# Interface.net
KiCad netlist of a schematic drawn in Altium Designer
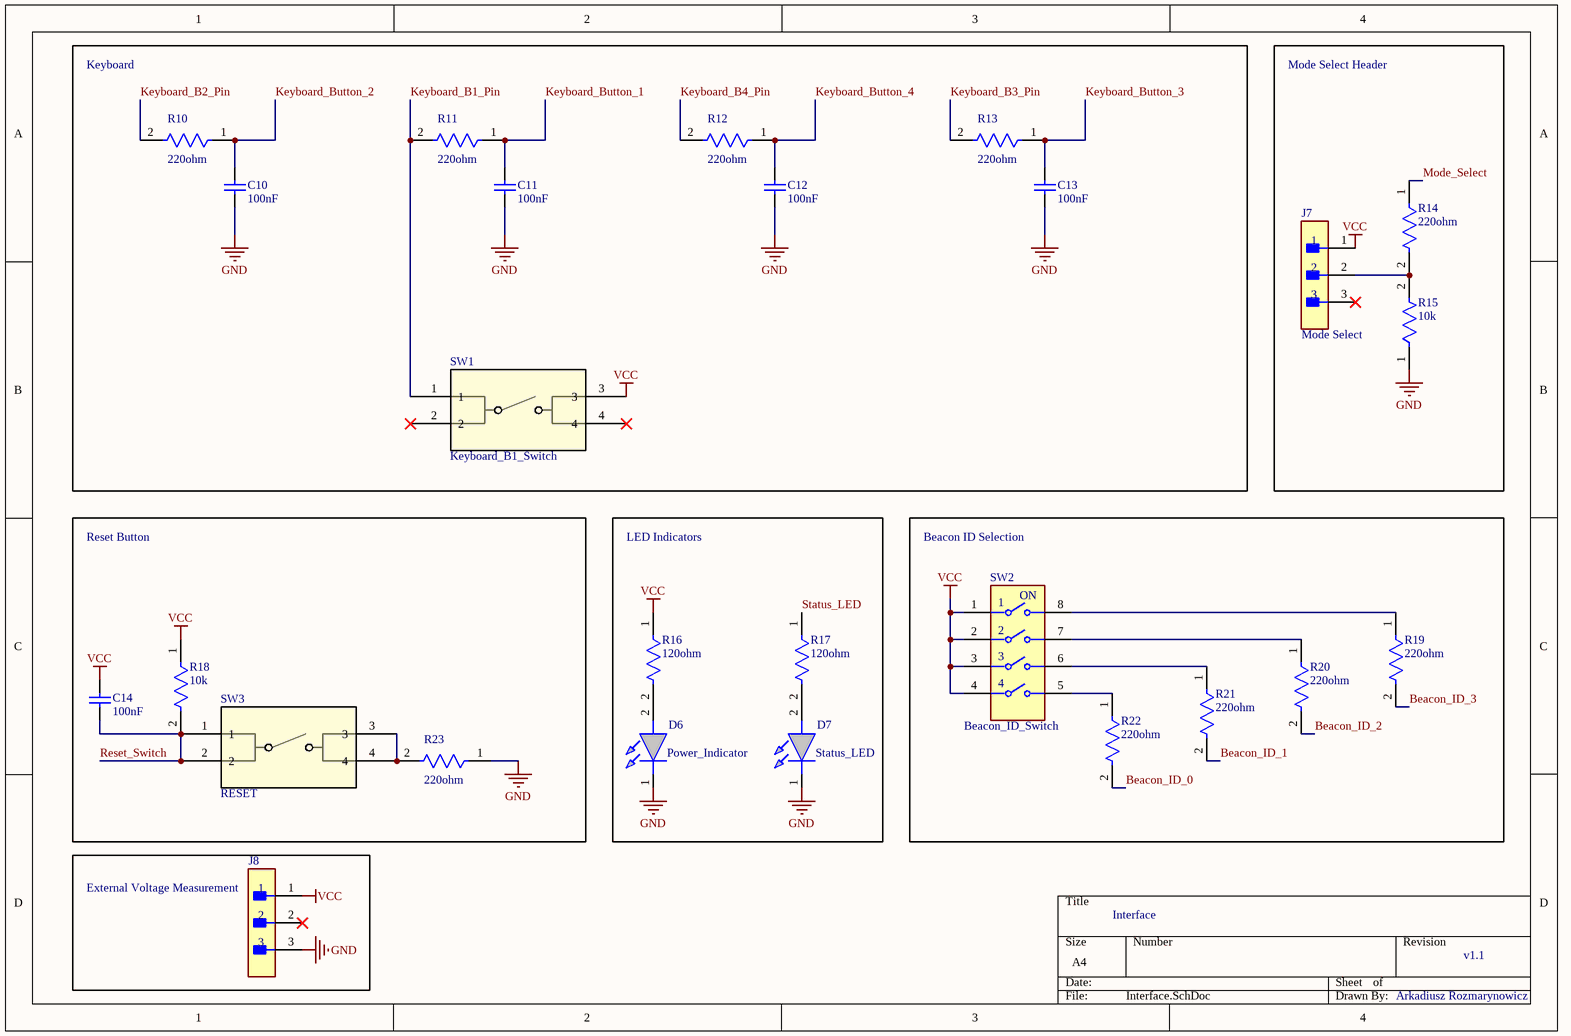
[diagram p0: Interface.SchDoc]

(export (version "E")
  (design (tool "Eeschema 10.0.6"))
  (components
    (comp (ref "C10")
      (value "100nF")
      (footprint "CAPC2013X145X48NL20T23")
      (fields (field (name "PART NUMBER") "VJ0805Y104KXAMR") (field (name "MANUFACTURER") "Vitramon"))
      (libsource (lib "Altium Content Vault") (part "CAP"))
    )
    (comp (ref "C11")
      (value "100nF")
      (footprint "CAPC2013X145X48NL20T23")
      (fields (field (name "PART NUMBER") "VJ0805Y104KXAMR") (field (name "MANUFACTURER") "Vitramon"))
      (libsource (lib "Altium Content Vault") (part "CAP"))
    )
    (comp (ref "C12")
      (value "100nF")
      (footprint "CAPC2013X145X48NL20T23")
      (fields (field (name "PART NUMBER") "VJ0805Y104KXAMR") (field (name "MANUFACTURER") "Vitramon"))
      (libsource (lib "Altium Content Vault") (part "CAP"))
    )
    (comp (ref "C13")
      (value "100nF")
      (footprint "CAPC2013X145X48NL20T23")
      (fields (field (name "PART NUMBER") "VJ0805Y104KXAMR") (field (name "MANUFACTURER") "Vitramon"))
      (libsource (lib "Altium Content Vault") (part "CAP"))
    )
    (comp (ref "C14")
      (value "100nF")
      (footprint "CAPC2013X145X48NL20T23")
      (fields (field (name "PART NUMBER") "VJ0805Y104KXAMR") (field (name "MANUFACTURER") "Vitramon"))
      (libsource (lib "Altium Content Vault") (part "CAP"))
    )
    (comp (ref "D6")
      (value "Power_Indicator")
      (footprint "LEDC2012X40N")
      (fields
        (field (name "MANUFACTURER_PART_NUMBER") "LS R976")
        (field (name "MOUSER PART NUMBER") "720-LSR976D5178")
      )
      (libsource (lib "LS_R976") (part "LS_R976"))
    )
    (comp (ref "D7")
      (value "Status_LED")
      (footprint "LEDC2012X40N")
      (fields
        (field (name "MANUFACTURER_PART_NUMBER") "LS R976")
        (field (name "MOUSER PART NUMBER") "720-LSR976D5178")
      )
      (libsource (lib "LS_R976") (part "LS_R976"))
    )
    (comp (ref "J7")
      (value "Mode Select")
      (footprint "FP-TMM-103-03-T-S-MFG")
      (description "CONN HEADER VERT 3POS 2MM")
      (libsource (lib "Altium Content Vault") (part "0d3f023dd272f625e17a2be33dea85f"))
    )
    (comp (ref "J8")
      (value "External Voltage Measurement")
      (footprint "FP-TMM-103-03-T-S-MFG")
      (description "CONN HEADER VERT 3POS 2MM")
      (libsource (lib "Altium Content Vault") (part "0d3f023dd272f625e17a2be33dea85f"))
    )
    (comp (ref "R10")
      (value "220ohm")
      (footprint "FP-CRGCQ0805-IPC_C")
      (description "CRGCQ0805 100KΩ 0.125W ±100ppm/°C 5% 150V")
      (fields
        (field (name "TOLERANCE") "0.05")
        (field (name "OCTOPART") "https://octopart.com/crgcq0805j100k-te+connectivity-91018199")
      )
      (libsource (lib "Altium Content Vault") (part "1029c3af85768c4190bb7ad29bc67b5"))
    )
    (comp (ref "R11")
      (value "220ohm")
      (footprint "FP-CRGCQ0805-IPC_C")
      (description "CRGCQ0805 100KΩ 0.125W ±100ppm/°C 5% 150V")
      (fields
        (field (name "TOLERANCE") "0.05")
        (field (name "OCTOPART") "https://octopart.com/crgcq0805j100k-te+connectivity-91018199")
      )
      (libsource (lib "Altium Content Vault") (part "1029c3af85768c4190bb7ad29bc67b5"))
    )
    (comp (ref "R12")
      (value "220ohm")
      (footprint "FP-CRGCQ0805-IPC_C")
      (description "CRGCQ0805 100KΩ 0.125W ±100ppm/°C 5% 150V")
      (fields
        (field (name "TOLERANCE") "0.05")
        (field (name "OCTOPART") "https://octopart.com/crgcq0805j100k-te+connectivity-91018199")
      )
      (libsource (lib "Altium Content Vault") (part "1029c3af85768c4190bb7ad29bc67b5"))
    )
    (comp (ref "R13")
      (value "220ohm")
      (footprint "FP-CRGCQ0805-IPC_C")
      (description "CRGCQ0805 100KΩ 0.125W ±100ppm/°C 5% 150V")
      (fields
        (field (name "TOLERANCE") "0.05")
        (field (name "OCTOPART") "https://octopart.com/crgcq0805j100k-te+connectivity-91018199")
      )
      (libsource (lib "Altium Content Vault") (part "1029c3af85768c4190bb7ad29bc67b5"))
    )
    (comp (ref "R14")
      (value "220ohm")
      (footprint "FP-CRGCQ0805-IPC_C")
      (description "CRGCQ0805 10KΩ 0.125W ±100ppm/°C 5% 150V")
      (fields
        (field (name "TOLERANCE") "0.05")
        (field (name "OCTOPART") "https://octopart.com/crgcq0805j100k-te+connectivity-91018199")
      )
      (libsource (lib "Altium Content Vault") (part "1029c3af85768c4190bb7ad29bc67b5"))
    )
    (comp (ref "R15")
      (value "10k")
      (footprint "FP-CRGCQ0805-IPC_C")
      (description "CRGCQ0805 10KΩ 0.125W ±100ppm/°C 5% 150V")
      (fields
        (field (name "TOLERANCE") "0.05")
        (field (name "OCTOPART") "https://octopart.com/crgcq0805j100k-te+connectivity-91018199")
      )
      (libsource (lib "Altium Content Vault") (part "1029c3af85768c4190bb7ad29bc67b5"))
    )
    (comp (ref "R16")
      (value "120ohm")
      (footprint "FP-CRGCQ0805-IPC_C")
      (description "CRGCQ0805 100KΩ 0.125W ±100ppm/°C 5% 150V")
      (fields
        (field (name "TOLERANCE") "0.05")
        (field (name "OCTOPART") "https://octopart.com/crgcq0805j100k-te+connectivity-91018199")
      )
      (libsource (lib "Altium Content Vault") (part "1029c3af85768c4190bb7ad29bc67b5"))
    )
    (comp (ref "R17")
      (value "120ohm")
      (footprint "FP-CRGCQ0805-IPC_C")
      (description "CRGCQ0805 100KΩ 0.125W ±100ppm/°C 5% 150V")
      (fields
        (field (name "TOLERANCE") "0.05")
        (field (name "OCTOPART") "https://octopart.com/crgcq0805j100k-te+connectivity-91018199")
      )
      (libsource (lib "Altium Content Vault") (part "1029c3af85768c4190bb7ad29bc67b5"))
    )
    (comp (ref "R18")
      (value "10k")
      (footprint "FP-CRGCQ0805-IPC_C")
      (description "CRGCQ0805 10KΩ 0.125W ±100ppm/°C 5% 150V")
      (fields
        (field (name "TOLERANCE") "0.05")
        (field (name "OCTOPART") "https://octopart.com/crgcq0805j100k-te+connectivity-91018199")
      )
      (libsource (lib "Altium Content Vault") (part "1029c3af85768c4190bb7ad29bc67b5"))
    )
    (comp (ref "R19")
      (value "220ohm")
      (footprint "FP-CRGCQ0805-IPC_C")
      (description "CRGCQ0805 10KΩ 0.125W ±100ppm/°C 5% 150V")
      (fields
        (field (name "TOLERANCE") "0.05")
        (field (name "OCTOPART") "https://octopart.com/crgcq0805j100k-te+connectivity-91018199")
      )
      (libsource (lib "Altium Content Vault") (part "1029c3af85768c4190bb7ad29bc67b5"))
    )
    (comp (ref "R20")
      (value "220ohm")
      (footprint "FP-CRGCQ0805-IPC_C")
      (description "CRGCQ0805 10KΩ 0.125W ±100ppm/°C 5% 150V")
      (fields
        (field (name "TOLERANCE") "0.05")
        (field (name "OCTOPART") "https://octopart.com/crgcq0805j100k-te+connectivity-91018199")
      )
      (libsource (lib "Altium Content Vault") (part "1029c3af85768c4190bb7ad29bc67b5"))
    )
    (comp (ref "R21")
      (value "220ohm")
      (footprint "FP-CRGCQ0805-IPC_C")
      (description "CRGCQ0805 10KΩ 0.125W ±100ppm/°C 5% 150V")
      (fields
        (field (name "TOLERANCE") "0.05")
        (field (name "OCTOPART") "https://octopart.com/crgcq0805j100k-te+connectivity-91018199")
      )
      (libsource (lib "Altium Content Vault") (part "1029c3af85768c4190bb7ad29bc67b5"))
    )
    (comp (ref "R22")
      (value "220ohm")
      (footprint "FP-CRGCQ0805-IPC_C")
      (description "CRGCQ0805 10KΩ 0.125W ±100ppm/°C 5% 150V")
      (fields
        (field (name "TOLERANCE") "0.05")
        (field (name "OCTOPART") "https://octopart.com/crgcq0805j100k-te+connectivity-91018199")
      )
      (libsource (lib "Altium Content Vault") (part "1029c3af85768c4190bb7ad29bc67b5"))
    )
    (comp (ref "R23")
      (value "220ohm")
      (footprint "FP-CRGCQ0805-IPC_C")
      (description "CRGCQ0805 100KΩ 0.125W ±100ppm/°C 5% 150V")
      (fields
        (field (name "TOLERANCE") "0.05")
        (field (name "OCTOPART") "https://octopart.com/crgcq0805j100k-te+connectivity-91018199")
      )
      (libsource (lib "Altium Content Vault") (part "1029c3af85768c4190bb7ad29bc67b5"))
    )
    (comp (ref "SW1")
      (value "Keyboard_B1_Switch")
      (footprint "SW4_FSM-5P23_TEC")
      (description "FSM4JSMAATR=TACTSWITCH,SMT,T&R")
      (fields
        (field (name "MANUFACTURER_PART_NUMBER") "1571563-4")
        (field (name "COPYRIGHT") "Copyright (C) 2025 Ultra Librarian. All rights reserved.")
      )
      (libsource (lib "FSM4JSMAATR") (part "1571563-4"))
    )
    (comp (ref "SW2")
      (value "Beacon_ID_Switch")
      (footprint "FP-A6S-4104-H-MFG")
      (description "SWITCH SLIDE DIP SPST 25MA 24V")
      (fields
        (field (name "OCTOPART") "https://octopart.com/a6s-4104-h-omron-1480027")
        (field (name "MANUFACTURER PART NUMBER") "A6S-4104-H")
      )
      (libsource (lib "Altium Content Vault") (part "113dad22f56f77360964ee595240726"))
    )
    (comp (ref "SW3")
      (value "RESET")
      (footprint "SW4_FSM-5P23_TEC")
      (description "FSM4JSMAATR=TACTSWITCH,SMT,T&R")
      (fields
        (field (name "MANUFACTURER_PART_NUMBER") "1571563-4")
        (field (name "COPYRIGHT") "Copyright (C) 2025 Ultra Librarian. All rights reserved.")
      )
      (libsource (lib "FSM4JSMAATR") (part "1571563-4"))
    )
  )
  (nets
    (net (code "1") (name "/Beacon_ID_0") (class "Default")
      (node (ref "R22") (pin "2") (pinfunction "2_2") (pintype "passive"))
    )
    (net (code "2") (name "/Beacon_ID_1") (class "Default")
      (node (ref "R21") (pin "2") (pinfunction "2_2") (pintype "passive"))
    )
    (net (code "3") (name "/Beacon_ID_2") (class "Default")
      (node (ref "R20") (pin "2") (pinfunction "2_2") (pintype "passive"))
    )
    (net (code "4") (name "/Beacon_ID_3") (class "Default")
      (node (ref "R19") (pin "2") (pinfunction "2_2") (pintype "passive"))
    )
    (net (code "5") (name "/Keyboard_B1_Pin") (class "Default")
      (node (ref "R11") (pin "2") (pinfunction "2_2") (pintype "passive"))
      (node (ref "SW1") (pin "1") (pinfunction "1_1") (pintype "passive"))
    )
    (net (code "6") (name "/Keyboard_B2_Pin") (class "Default")
      (node (ref "R10") (pin "2") (pinfunction "2_2") (pintype "passive"))
    )
    (net (code "7") (name "/Keyboard_B3_Pin") (class "Default")
      (node (ref "R13") (pin "2") (pinfunction "2_2") (pintype "passive"))
    )
    (net (code "8") (name "/Keyboard_B4_Pin") (class "Default")
      (node (ref "R12") (pin "2") (pinfunction "2_2") (pintype "passive"))
    )
    (net (code "9") (name "/Keyboard_Button_1") (class "Default")
      (node (ref "C11") (pin "2") (pinfunction "2_2") (pintype "passive"))
      (node (ref "R11") (pin "1") (pinfunction "1_1") (pintype "passive"))
    )
    (net (code "10") (name "/Keyboard_Button_2") (class "Default")
      (node (ref "C10") (pin "2") (pinfunction "2_2") (pintype "passive"))
      (node (ref "R10") (pin "1") (pinfunction "1_1") (pintype "passive"))
    )
    (net (code "11") (name "/Keyboard_Button_3") (class "Default")
      (node (ref "C13") (pin "2") (pinfunction "2_2") (pintype "passive"))
      (node (ref "R13") (pin "1") (pinfunction "1_1") (pintype "passive"))
    )
    (net (code "12") (name "/Keyboard_Button_4") (class "Default")
      (node (ref "C12") (pin "2") (pinfunction "2_2") (pintype "passive"))
      (node (ref "R12") (pin "1") (pinfunction "1_1") (pintype "passive"))
    )
    (net (code "13") (name "/Mode_Select") (class "Default")
      (node (ref "R14") (pin "1") (pinfunction "1_1") (pintype "passive"))
    )
    (net (code "14") (name "/Reset_Switch") (class "Default")
      (node (ref "C14") (pin "1") (pinfunction "1_1") (pintype "passive"))
      (node (ref "R18") (pin "2") (pinfunction "2_2") (pintype "passive"))
      (node (ref "SW3") (pin "1") (pinfunction "1_1") (pintype "passive"))
      (node (ref "SW3") (pin "2") (pinfunction "2_2") (pintype "passive"))
    )
    (net (code "15") (name "/Status_LED") (class "Default")
      (node (ref "R17") (pin "1") (pinfunction "1_1") (pintype "passive"))
    )
    (net (code "16") (name "GND") (class "Default")
      (node (ref "C10") (pin "1") (pinfunction "1_1") (pintype "passive"))
      (node (ref "C11") (pin "1") (pinfunction "1_1") (pintype "passive"))
      (node (ref "C12") (pin "1") (pinfunction "1_1") (pintype "passive"))
      (node (ref "C13") (pin "1") (pinfunction "1_1") (pintype "passive"))
      (node (ref "D6") (pin "1") (pinfunction "K_1") (pintype "passive"))
      (node (ref "D7") (pin "1") (pinfunction "K_1") (pintype "passive"))
      (node (ref "J8") (pin "3") (pinfunction "3_3") (pintype "passive"))
      (node (ref "R15") (pin "1") (pinfunction "1_1") (pintype "passive"))
      (node (ref "R23") (pin "1") (pinfunction "1_1") (pintype "passive"))
    )
    (net (code "17") (name "Net-(D6-A)") (class "Default")
      (node (ref "D6") (pin "2") (pinfunction "A_2") (pintype "passive"))
      (node (ref "R16") (pin "2") (pinfunction "2_2") (pintype "passive"))
    )
    (net (code "18") (name "Net-(D7-A)") (class "Default")
      (node (ref "D7") (pin "2") (pinfunction "A_2") (pintype "passive"))
      (node (ref "R17") (pin "2") (pinfunction "2_2") (pintype "passive"))
    )
    (net (code "19") (name "Net-(J7-Pad2)") (class "Default")
      (node (ref "J7") (pin "2") (pinfunction "2_2") (pintype "passive"))
      (node (ref "R14") (pin "2") (pinfunction "2_2") (pintype "passive"))
      (node (ref "R15") (pin "2") (pinfunction "2_2") (pintype "passive"))
    )
    (net (code "20") (name "Net-(R19-Pad1)") (class "Default")
      (node (ref "R19") (pin "1") (pinfunction "1_1") (pintype "passive"))
      (node (ref "SW2") (pin "8") (pinfunction "8_8") (pintype "passive"))
    )
    (net (code "21") (name "Net-(R20-Pad1)") (class "Default")
      (node (ref "R20") (pin "1") (pinfunction "1_1") (pintype "passive"))
      (node (ref "SW2") (pin "7") (pinfunction "7_7") (pintype "passive"))
    )
    (net (code "22") (name "Net-(R21-Pad1)") (class "Default")
      (node (ref "R21") (pin "1") (pinfunction "1_1") (pintype "passive"))
      (node (ref "SW2") (pin "6") (pinfunction "6_6") (pintype "passive"))
    )
    (net (code "23") (name "Net-(R22-Pad1)") (class "Default")
      (node (ref "R22") (pin "1") (pinfunction "1_1") (pintype "passive"))
      (node (ref "SW2") (pin "5") (pinfunction "5_5") (pintype "passive"))
    )
    (net (code "24") (name "Net-(R23-Pad2)") (class "Default")
      (node (ref "R23") (pin "2") (pinfunction "2_2") (pintype "passive"))
      (node (ref "SW3") (pin "3") (pinfunction "3_3") (pintype "passive"))
      (node (ref "SW3") (pin "4") (pinfunction "4_4") (pintype "passive"))
    )
    (net (code "25") (name "VCC") (class "Default")
      (node (ref "C14") (pin "2") (pinfunction "2_2") (pintype "passive"))
      (node (ref "J7") (pin "1") (pinfunction "1_1") (pintype "passive"))
      (node (ref "J8") (pin "1") (pinfunction "1_1") (pintype "passive"))
      (node (ref "R16") (pin "1") (pinfunction "1_1") (pintype "passive"))
      (node (ref "R18") (pin "1") (pinfunction "1_1") (pintype "passive"))
      (node (ref "SW1") (pin "3") (pinfunction "3_3") (pintype "passive"))
      (node (ref "SW2") (pin "1") (pinfunction "1_1") (pintype "passive"))
      (node (ref "SW2") (pin "2") (pinfunction "2_2") (pintype "passive"))
      (node (ref "SW2") (pin "3") (pinfunction "3_3") (pintype "passive"))
      (node (ref "SW2") (pin "4") (pinfunction "4_4") (pintype "passive"))
    )
    (net (code "26") (name "unconnected-(J7-Pad3)") (class "Default")
      (node (ref "J7") (pin "3") (pinfunction "3_3") (pintype "passive+no_connect"))
    )
    (net (code "27") (name "unconnected-(J8-Pad2)") (class "Default")
      (node (ref "J8") (pin "2") (pinfunction "2_2") (pintype "passive+no_connect"))
    )
    (net (code "28") (name "unconnected-(SW1-Pad2)") (class "Default")
      (node (ref "SW1") (pin "2") (pinfunction "2_2") (pintype "passive+no_connect"))
    )
    (net (code "29") (name "unconnected-(SW1-Pad4)") (class "Default")
      (node (ref "SW1") (pin "4") (pinfunction "4_4") (pintype "passive+no_connect"))
    )
  )
)
